# MCU.net
KiCad netlist of a schematic drawn in Altium Designer
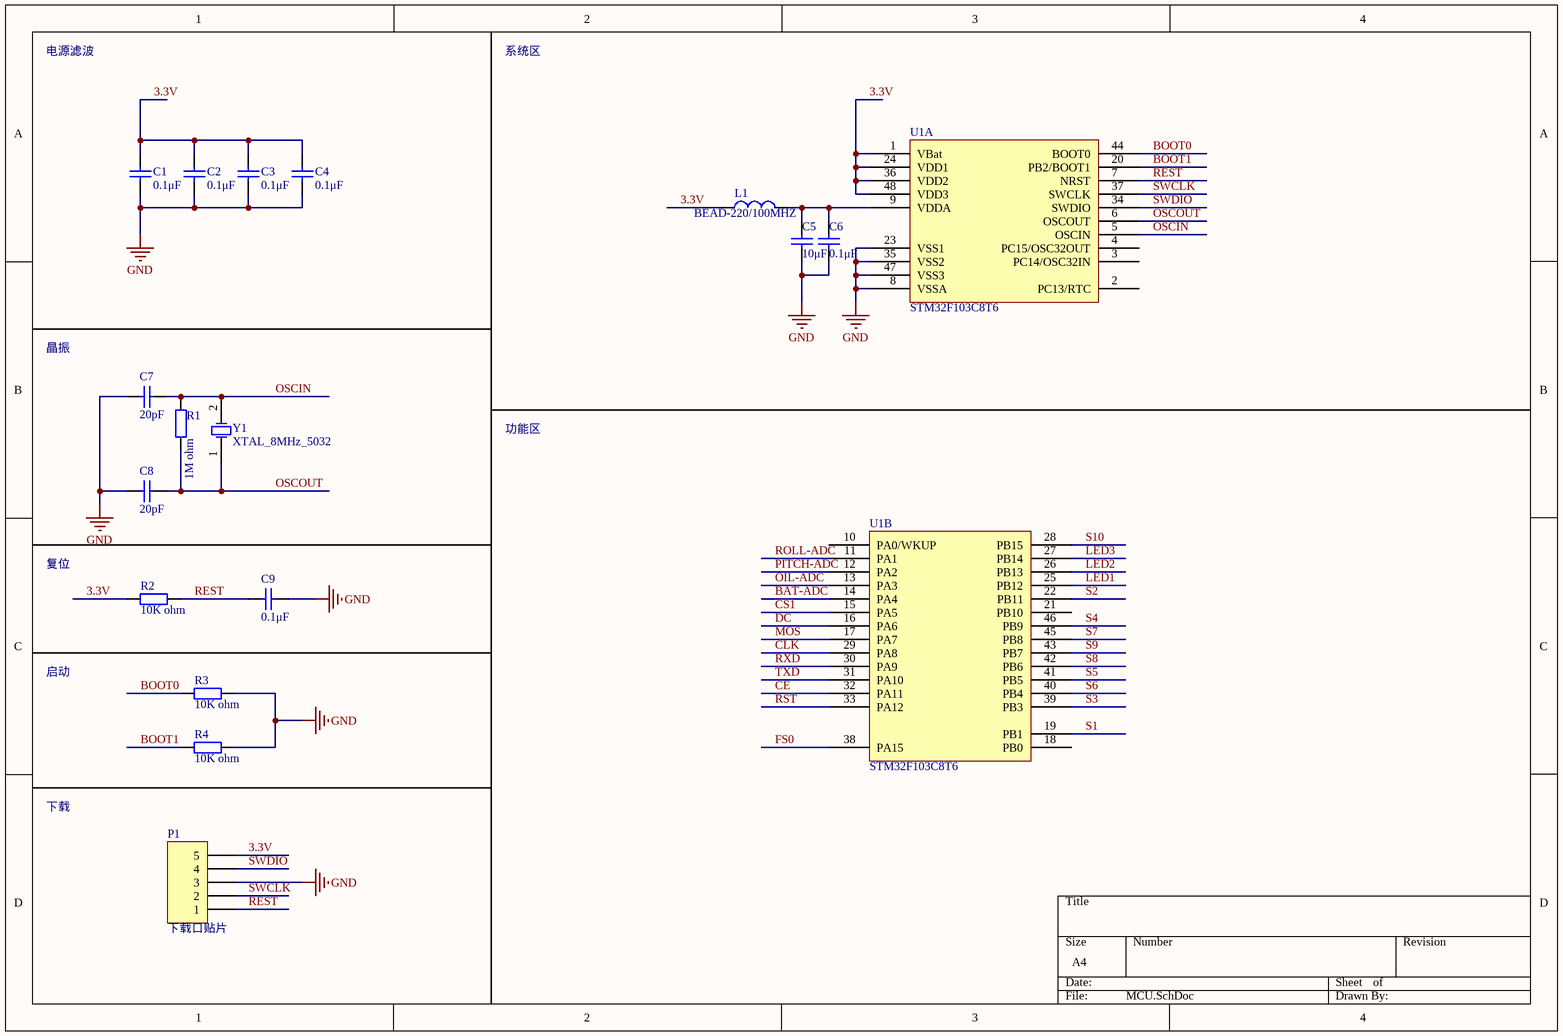
[diagram p0: MCU.SchDoc]

(export (version "E")
  (design (tool "Eeschema 10.0.6"))
  (components
    (comp (ref "C1")
      (value "0.1μF")
      (footprint "0603C")
      (description "0.1μF_50V,X7R,±5%")
      (libsource (lib "Yang_Lib") (part "Cap_0.1μF_50V_0603"))
    )
    (comp (ref "C2")
      (value "0.1μF")
      (footprint "0603C")
      (description "0.1μF_50V,X7R,±5%")
      (libsource (lib "Yang_Lib") (part "Cap_0.1μF_50V_0603"))
    )
    (comp (ref "C3")
      (value "0.1μF")
      (footprint "0603C")
      (description "0.1μF_50V,X7R,±5%")
      (libsource (lib "Yang_Lib") (part "Cap_0.1μF_50V_0603"))
    )
    (comp (ref "C4")
      (value "0.1μF")
      (footprint "0603C")
      (description "0.1μF_50V,X7R,±5%")
      (libsource (lib "Yang_Lib") (part "Cap_0.1μF_50V_0603"))
    )
    (comp (ref "C5")
      (value "10μF")
      (footprint "0603C")
      (description "10μF_35V,X5R,20%")
      (libsource (lib "Yang_Lib") (part "Cap_10μF_35V_0603"))
    )
    (comp (ref "C6")
      (value "0.1μF")
      (footprint "0603C")
      (description "0.1μF_50V,X7R,±5%")
      (libsource (lib "Yang_Lib") (part "Cap_0.1μF_50V_0603"))
    )
    (comp (ref "C7")
      (value "20pF")
      (footprint "0603C")
      (description "20pF_50V,CH,±5%")
      (libsource (lib "Yang_Lib") (part "Cap_20pF_50V_0603"))
    )
    (comp (ref "C8")
      (value "20pF")
      (footprint "0603C")
      (description "20pF_50V,CH,±5%")
      (libsource (lib "Yang_Lib") (part "Cap_20pF_50V_0603"))
    )
    (comp (ref "C9")
      (value "0.1μF")
      (footprint "0603C")
      (description "0.1μF_50V,X7R,±5%")
      (libsource (lib "Yang_Lib") (part "Cap_0.1μF_50V_0603"))
    )
    (comp (ref "L1")
      (value "BEAD-220/100MHZ")
      (footprint "0603R")
      (libsource (lib "Yang_Lib") (part "BEAD-220/100MHZ_0603"))
    )
    (comp (ref "P1")
      (value "下载口贴片")
      (footprint "HDR1X5 - danceng")
      (description "DAP下载口贴片")
      (libsource (lib "Yang_Lib") (part "DAP下载口贴片"))
    )
    (comp (ref "R1")
      (value "1M ohm")
      (footprint "0603R")
      (description "1M ohm,1%")
      (libsource (lib "Yang_Lib") (part "Res_1M ohm_0603"))
    )
    (comp (ref "R2")
      (value "10K ohm")
      (footprint "0603R")
      (description "10K ohm,1%")
      (libsource (lib "Yang_Lib") (part "Res_10K ohm_0603"))
    )
    (comp (ref "R3")
      (value "10K ohm")
      (footprint "0603R")
      (description "10K ohm,1%")
      (libsource (lib "Yang_Lib") (part "Res_10K ohm_0603"))
    )
    (comp (ref "R4")
      (value "10K ohm")
      (footprint "0603R")
      (description "10K ohm,1%")
      (libsource (lib "Yang_Lib") (part "Res_10K ohm_0603"))
    )
    (comp (ref "U1")
      (value "STM32F103C8T6")
      (footprint "LQFP48")
      (libsource (lib "Yang_Lib") (part "STM32F103C8T6"))
    )
    (comp (ref "Y1")
      (value "XTAL_8MHz_5032")
      (footprint "5032")
      (description "XTAL_8MHz")
      (libsource (lib "Yang_Lib") (part "XTAL_8MHz_5032"))
    )
  )
  (nets
    (net (code "1") (name "/3.3V") (class "Default")
      (node (ref "C1") (pin "2") (pinfunction "2_2") (pintype "passive"))
      (node (ref "C2") (pin "2") (pinfunction "2_2") (pintype "passive"))
      (node (ref "C3") (pin "2") (pinfunction "2_2") (pintype "passive"))
      (node (ref "C4") (pin "2") (pinfunction "2_2") (pintype "passive"))
      (node (ref "L1") (pin "1") (pinfunction "1_1") (pintype "passive"))
      (node (ref "P1") (pin "5") (pinfunction "5_5") (pintype "passive"))
      (node (ref "R2") (pin "1") (pinfunction "1_1") (pintype "passive"))
      (node (ref "U1") (pin "1") (pinfunction "VBat_1") (pintype "passive"))
      (node (ref "U1") (pin "24") (pinfunction "VDD1_24") (pintype "passive"))
      (node (ref "U1") (pin "36") (pinfunction "VDD2_36") (pintype "passive"))
      (node (ref "U1") (pin "48") (pinfunction "VDD3_48") (pintype "passive"))
    )
    (net (code "2") (name "/BAT-ADC") (class "Default")
      (node (ref "U1") (pin "14") (pinfunction "PA4_14") (pintype "passive"))
    )
    (net (code "3") (name "/BOOT0") (class "Default")
      (node (ref "R3") (pin "1") (pinfunction "1_1") (pintype "passive"))
      (node (ref "U1") (pin "44") (pinfunction "BOOT0_44") (pintype "passive"))
    )
    (net (code "4") (name "/BOOT1") (class "Default")
      (node (ref "R4") (pin "1") (pinfunction "1_1") (pintype "passive"))
      (node (ref "U1") (pin "20") (pinfunction "PB2/BOOT1_20") (pintype "passive"))
    )
    (net (code "5") (name "/CE") (class "Default")
      (node (ref "U1") (pin "32") (pinfunction "PA11_32") (pintype "passive"))
    )
    (net (code "6") (name "/CLK") (class "Default")
      (node (ref "U1") (pin "29") (pinfunction "PA8_29") (pintype "passive"))
    )
    (net (code "7") (name "/CS1") (class "Default")
      (node (ref "U1") (pin "15") (pinfunction "PA5_15") (pintype "passive"))
    )
    (net (code "8") (name "/DC") (class "Default")
      (node (ref "U1") (pin "16") (pinfunction "PA6_16") (pintype "passive"))
    )
    (net (code "9") (name "/FS0") (class "Default")
      (node (ref "U1") (pin "38") (pinfunction "PA15_38") (pintype "passive"))
    )
    (net (code "10") (name "/LED1") (class "Default")
      (node (ref "U1") (pin "25") (pinfunction "PB12_25") (pintype "passive"))
    )
    (net (code "11") (name "/LED2") (class "Default")
      (node (ref "U1") (pin "26") (pinfunction "PB13_26") (pintype "passive"))
    )
    (net (code "12") (name "/LED3") (class "Default")
      (node (ref "U1") (pin "27") (pinfunction "PB14_27") (pintype "passive"))
    )
    (net (code "13") (name "/MOS") (class "Default")
      (node (ref "U1") (pin "17") (pinfunction "PA7_17") (pintype "passive"))
    )
    (net (code "14") (name "/OIL-ADC") (class "Default")
      (node (ref "U1") (pin "13") (pinfunction "PA3_13") (pintype "passive"))
    )
    (net (code "15") (name "/OSCIN") (class "Default")
      (node (ref "C7") (pin "1") (pinfunction "1_1") (pintype "passive"))
      (node (ref "R1") (pin "2") (pinfunction "2_2") (pintype "passive"))
      (node (ref "U1") (pin "5") (pinfunction "OSCIN_5") (pintype "passive"))
      (node (ref "Y1") (pin "2") (pinfunction "OSC2_2") (pintype "passive"))
    )
    (net (code "16") (name "/OSCOUT") (class "Default")
      (node (ref "C8") (pin "1") (pinfunction "1_1") (pintype "passive"))
      (node (ref "R1") (pin "1") (pinfunction "1_1") (pintype "passive"))
      (node (ref "U1") (pin "6") (pinfunction "OSCOUT_6") (pintype "passive"))
      (node (ref "Y1") (pin "1") (pinfunction "OSC1_1") (pintype "passive"))
    )
    (net (code "17") (name "/PITCH-ADC") (class "Default")
      (node (ref "U1") (pin "12") (pinfunction "PA2_12") (pintype "passive"))
    )
    (net (code "18") (name "/REST") (class "Default")
      (node (ref "C9") (pin "2") (pinfunction "2_2") (pintype "passive"))
      (node (ref "P1") (pin "1") (pinfunction "1_1") (pintype "passive"))
      (node (ref "R2") (pin "2") (pinfunction "2_2") (pintype "passive"))
      (node (ref "U1") (pin "7") (pinfunction "NRST_7") (pintype "passive"))
    )
    (net (code "19") (name "/ROLL-ADC") (class "Default")
      (node (ref "U1") (pin "11") (pinfunction "PA1_11") (pintype "passive"))
    )
    (net (code "20") (name "/RST") (class "Default")
      (node (ref "U1") (pin "33") (pinfunction "PA12_33") (pintype "passive"))
    )
    (net (code "21") (name "/RXD") (class "Default")
      (node (ref "U1") (pin "30") (pinfunction "PA9_30") (pintype "passive"))
    )
    (net (code "22") (name "/S1") (class "Default")
      (node (ref "U1") (pin "19") (pinfunction "PB1_19") (pintype "passive"))
    )
    (net (code "23") (name "/S2") (class "Default")
      (node (ref "U1") (pin "22") (pinfunction "PB11_22") (pintype "passive"))
    )
    (net (code "24") (name "/S3") (class "Default")
      (node (ref "U1") (pin "39") (pinfunction "PB3_39") (pintype "passive"))
    )
    (net (code "25") (name "/S4") (class "Default")
      (node (ref "U1") (pin "46") (pinfunction "PB9_46") (pintype "passive"))
    )
    (net (code "26") (name "/S5") (class "Default")
      (node (ref "U1") (pin "41") (pinfunction "PB5_41") (pintype "passive"))
    )
    (net (code "27") (name "/S6") (class "Default")
      (node (ref "U1") (pin "40") (pinfunction "PB4_40") (pintype "passive"))
    )
    (net (code "28") (name "/S7") (class "Default")
      (node (ref "U1") (pin "45") (pinfunction "PB8_45") (pintype "passive"))
    )
    (net (code "29") (name "/S8") (class "Default")
      (node (ref "U1") (pin "42") (pinfunction "PB6_42") (pintype "passive"))
    )
    (net (code "30") (name "/S9") (class "Default")
      (node (ref "U1") (pin "43") (pinfunction "PB7_43") (pintype "passive"))
    )
    (net (code "31") (name "/S10") (class "Default")
      (node (ref "U1") (pin "28") (pinfunction "PB15_28") (pintype "passive"))
    )
    (net (code "32") (name "/SWCLK") (class "Default")
      (node (ref "P1") (pin "2") (pinfunction "2_2") (pintype "passive"))
      (node (ref "U1") (pin "37") (pinfunction "SWCLK_37") (pintype "passive"))
    )
    (net (code "33") (name "/SWDIO") (class "Default")
      (node (ref "P1") (pin "4") (pinfunction "4_4") (pintype "passive"))
      (node (ref "U1") (pin "34") (pinfunction "SWDIO_34") (pintype "passive"))
    )
    (net (code "34") (name "/TXD") (class "Default")
      (node (ref "U1") (pin "31") (pinfunction "PA10_31") (pintype "passive"))
    )
    (net (code "35") (name "GND") (class "Default")
      (node (ref "C1") (pin "1") (pinfunction "1_1") (pintype "passive"))
      (node (ref "C2") (pin "1") (pinfunction "1_1") (pintype "passive"))
      (node (ref "C3") (pin "1") (pinfunction "1_1") (pintype "passive"))
      (node (ref "C4") (pin "1") (pinfunction "1_1") (pintype "passive"))
      (node (ref "C5") (pin "1") (pinfunction "1_1") (pintype "passive"))
      (node (ref "C6") (pin "1") (pinfunction "1_1") (pintype "passive"))
      (node (ref "C7") (pin "2") (pinfunction "2_2") (pintype "passive"))
      (node (ref "C8") (pin "2") (pinfunction "2_2") (pintype "passive"))
      (node (ref "C9") (pin "1") (pinfunction "1_1") (pintype "passive"))
      (node (ref "P1") (pin "3") (pinfunction "3_3") (pintype "passive"))
      (node (ref "R3") (pin "2") (pinfunction "2_2") (pintype "passive"))
      (node (ref "R4") (pin "2") (pinfunction "2_2") (pintype "passive"))
      (node (ref "U1") (pin "23") (pinfunction "VSS1_23") (pintype "passive"))
      (node (ref "U1") (pin "35") (pinfunction "VSS2_35") (pintype "passive"))
      (node (ref "U1") (pin "47") (pinfunction "VSS3_47") (pintype "passive"))
      (node (ref "U1") (pin "8") (pinfunction "VSSA_8") (pintype "passive"))
    )
    (net (code "36") (name "Net-(U1A-VDDA)") (class "Default")
      (node (ref "C5") (pin "2") (pinfunction "2_2") (pintype "passive"))
      (node (ref "C6") (pin "2") (pinfunction "2_2") (pintype "passive"))
      (node (ref "L1") (pin "2") (pinfunction "2_2") (pintype "passive"))
      (node (ref "U1") (pin "9") (pinfunction "VDDA_9") (pintype "passive"))
    )
    (net (code "37") (name "unconnected-(U1A-PC13{slash}RTC-Pad2)") (class "Default")
      (node (ref "U1") (pin "2") (pinfunction "PC13/RTC_2") (pintype "passive"))
    )
    (net (code "38") (name "unconnected-(U1A-PC14{slash}OSC32IN-Pad3)") (class "Default")
      (node (ref "U1") (pin "3") (pinfunction "PC14/OSC32IN_3") (pintype "passive"))
    )
    (net (code "39") (name "unconnected-(U1A-PC15{slash}OSC32OUT-Pad4)") (class "Default")
      (node (ref "U1") (pin "4") (pinfunction "PC15/OSC32OUT_4") (pintype "passive"))
    )
    (net (code "40") (name "unconnected-(U1B-PA0{slash}WKUP-Pad10)") (class "Default")
      (node (ref "U1") (pin "10") (pinfunction "PA0/WKUP_10") (pintype "passive"))
    )
    (net (code "41") (name "unconnected-(U1B-PB0-Pad18)") (class "Default")
      (node (ref "U1") (pin "18") (pinfunction "PB0_18") (pintype "passive"))
    )
    (net (code "42") (name "unconnected-(U1B-PB10-Pad21)") (class "Default")
      (node (ref "U1") (pin "21") (pinfunction "PB10_21") (pintype "passive"))
    )
  )
)
